# LED.net
KiCad netlist of a schematic drawn in Altium Designer
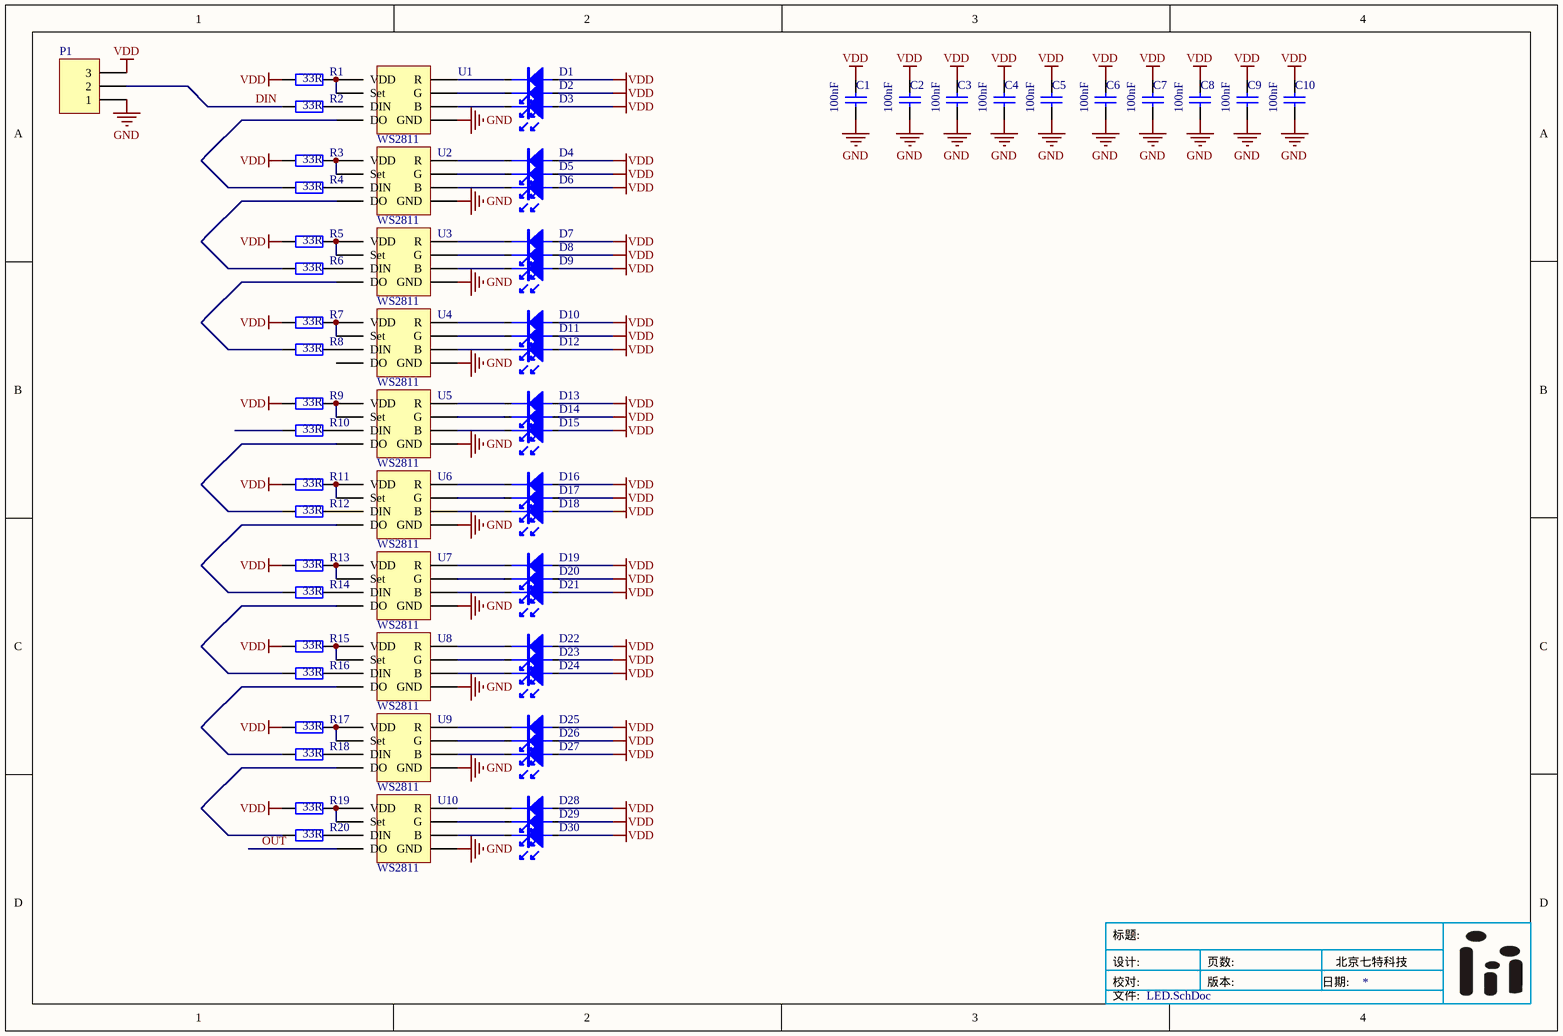
[diagram p0: LED.SchDoc]

(export (version "E")
  (design (tool "Eeschema 10.0.6"))
  (components
    (comp (ref "C1")
      (value "100nF")
      (footprint "1608C")
      (description "Capacitor")
      (fields (field (name "PUBLISHER") "Altium Limited"))
      (libsource (lib "*") (part "Cap"))
    )
    (comp (ref "C2")
      (value "100nF")
      (footprint "1608C")
      (description "Capacitor")
      (fields (field (name "PUBLISHER") "Altium Limited"))
      (libsource (lib "*") (part "Cap"))
    )
    (comp (ref "C3")
      (value "100nF")
      (footprint "1608C")
      (description "Capacitor")
      (fields (field (name "PUBLISHER") "Altium Limited"))
      (libsource (lib "*") (part "Cap"))
    )
    (comp (ref "C4")
      (value "100nF")
      (footprint "1608C")
      (description "Capacitor")
      (fields (field (name "PUBLISHER") "Altium Limited"))
      (libsource (lib "*") (part "Cap"))
    )
    (comp (ref "C5")
      (value "100nF")
      (footprint "1608C")
      (description "Capacitor")
      (fields (field (name "PUBLISHER") "Altium Limited"))
      (libsource (lib "*") (part "Cap"))
    )
    (comp (ref "C6")
      (value "100nF")
      (footprint "1608C")
      (description "Capacitor")
      (fields (field (name "PUBLISHER") "Altium Limited"))
      (libsource (lib "*") (part "Cap"))
    )
    (comp (ref "C7")
      (value "100nF")
      (footprint "1608C")
      (description "Capacitor")
      (fields (field (name "PUBLISHER") "Altium Limited"))
      (libsource (lib "*") (part "Cap"))
    )
    (comp (ref "C8")
      (value "100nF")
      (footprint "1608C")
      (description "Capacitor")
      (fields (field (name "PUBLISHER") "Altium Limited"))
      (libsource (lib "*") (part "Cap"))
    )
    (comp (ref "C9")
      (value "100nF")
      (footprint "1608C")
      (description "Capacitor")
      (fields (field (name "PUBLISHER") "Altium Limited"))
      (libsource (lib "*") (part "Cap"))
    )
    (comp (ref "C10")
      (value "100nF")
      (footprint "1608C")
      (description "Capacitor")
      (fields (field (name "PUBLISHER") "Altium Limited"))
      (libsource (lib "*") (part "Cap"))
    )
    (comp (ref "D1") (value "~") (footprint "LEDN/5S") (libsource (lib "*") (part "LED")))
    (comp (ref "D2") (value "~") (footprint "LEDN/5S") (libsource (lib "*") (part "LED")))
    (comp (ref "D3") (value "~") (footprint "LEDN/5S") (libsource (lib "*") (part "LED")))
    (comp (ref "D4") (value "~") (footprint "LEDN/5S") (libsource (lib "*") (part "LED")))
    (comp (ref "D5") (value "~") (footprint "LEDN/5S") (libsource (lib "*") (part "LED")))
    (comp (ref "D6") (value "~") (footprint "LEDN/5S") (libsource (lib "*") (part "LED")))
    (comp (ref "D7") (value "~") (footprint "LEDN/5S") (libsource (lib "*") (part "LED")))
    (comp (ref "D8") (value "~") (footprint "LEDN/5S") (libsource (lib "*") (part "LED")))
    (comp (ref "D9") (value "~") (footprint "LEDN/5S") (libsource (lib "*") (part "LED")))
    (comp (ref "D10") (value "~") (footprint "LEDN/5S") (libsource (lib "*") (part "LED")))
    (comp (ref "D11") (value "~") (footprint "LEDN/5S") (libsource (lib "*") (part "LED")))
    (comp (ref "D12") (value "~") (footprint "LEDN/5S") (libsource (lib "*") (part "LED")))
    (comp (ref "D13") (value "~") (footprint "LEDN/5S") (libsource (lib "*") (part "LED")))
    (comp (ref "D14") (value "~") (footprint "LEDN/5S") (libsource (lib "*") (part "LED")))
    (comp (ref "D15") (value "~") (footprint "LEDN/5S") (libsource (lib "*") (part "LED")))
    (comp (ref "D16") (value "~") (footprint "LEDN/5S") (libsource (lib "*") (part "LED")))
    (comp (ref "D17") (value "~") (footprint "LEDN/5S") (libsource (lib "*") (part "LED")))
    (comp (ref "D18") (value "~") (footprint "LEDN/5S") (libsource (lib "*") (part "LED")))
    (comp (ref "D19") (value "~") (footprint "LEDN/5S") (libsource (lib "*") (part "LED")))
    (comp (ref "D20") (value "~") (footprint "LEDN/5S") (libsource (lib "*") (part "LED")))
    (comp (ref "D21") (value "~") (footprint "LEDN/5S") (libsource (lib "*") (part "LED")))
    (comp (ref "D22") (value "~") (footprint "LEDN/5S") (libsource (lib "*") (part "LED")))
    (comp (ref "D23") (value "~") (footprint "LEDN/5S") (libsource (lib "*") (part "LED")))
    (comp (ref "D24") (value "~") (footprint "LEDN/5S") (libsource (lib "*") (part "LED")))
    (comp (ref "D25") (value "~") (footprint "LEDN/5S") (libsource (lib "*") (part "LED")))
    (comp (ref "D26") (value "~") (footprint "LEDN/5S") (libsource (lib "*") (part "LED")))
    (comp (ref "D27") (value "~") (footprint "LEDN/5S") (libsource (lib "*") (part "LED")))
    (comp (ref "D28") (value "~") (footprint "LEDN/5S") (libsource (lib "*") (part "LED")))
    (comp (ref "D29") (value "~") (footprint "LEDN/5S") (libsource (lib "*") (part "LED")))
    (comp (ref "D30") (value "~") (footprint "LEDN/5S") (libsource (lib "*") (part "LED")))
    (comp (ref "P1")
      (value "~")
      (footprint "5264-3")
      (description "Header, 3-Pin")
      (fields (field (name "PUBLISHER") "Altium Limited"))
      (libsource (lib "Miscellaneous Connectors") (part "Header 3"))
    )
    (comp (ref "R1")
      (value "33R")
      (footprint "1608")
      (description "Resistor")
      (fields (field (name "PUBLISHER") "Altium Limited"))
      (libsource (lib "*") (part "Res2"))
    )
    (comp (ref "R2")
      (value "33R")
      (footprint "1608")
      (description "Resistor")
      (fields (field (name "PUBLISHER") "Altium Limited"))
      (libsource (lib "*") (part "Res2"))
    )
    (comp (ref "R3")
      (value "33R")
      (footprint "1608")
      (description "Resistor")
      (fields (field (name "PUBLISHER") "Altium Limited"))
      (libsource (lib "*") (part "Res2"))
    )
    (comp (ref "R4")
      (value "33R")
      (footprint "1608")
      (description "Resistor")
      (fields (field (name "PUBLISHER") "Altium Limited"))
      (libsource (lib "*") (part "Res2"))
    )
    (comp (ref "R5")
      (value "33R")
      (footprint "1608")
      (description "Resistor")
      (fields (field (name "PUBLISHER") "Altium Limited"))
      (libsource (lib "*") (part "Res2"))
    )
    (comp (ref "R6")
      (value "33R")
      (footprint "1608")
      (description "Resistor")
      (fields (field (name "PUBLISHER") "Altium Limited"))
      (libsource (lib "*") (part "Res2"))
    )
    (comp (ref "R7")
      (value "33R")
      (footprint "1608")
      (description "Resistor")
      (fields (field (name "PUBLISHER") "Altium Limited"))
      (libsource (lib "*") (part "Res2"))
    )
    (comp (ref "R8")
      (value "33R")
      (footprint "1608")
      (description "Resistor")
      (fields (field (name "PUBLISHER") "Altium Limited"))
      (libsource (lib "*") (part "Res2"))
    )
    (comp (ref "R9")
      (value "33R")
      (footprint "1608")
      (description "Resistor")
      (fields (field (name "PUBLISHER") "Altium Limited"))
      (libsource (lib "*") (part "Res2"))
    )
    (comp (ref "R10")
      (value "33R")
      (footprint "1608")
      (description "Resistor")
      (fields (field (name "PUBLISHER") "Altium Limited"))
      (libsource (lib "*") (part "Res2"))
    )
    (comp (ref "R11")
      (value "33R")
      (footprint "1608")
      (description "Resistor")
      (fields (field (name "PUBLISHER") "Altium Limited"))
      (libsource (lib "*") (part "Res2"))
    )
    (comp (ref "R12")
      (value "33R")
      (footprint "1608")
      (description "Resistor")
      (fields (field (name "PUBLISHER") "Altium Limited"))
      (libsource (lib "*") (part "Res2"))
    )
    (comp (ref "R13")
      (value "33R")
      (footprint "1608")
      (description "Resistor")
      (fields (field (name "PUBLISHER") "Altium Limited"))
      (libsource (lib "*") (part "Res2"))
    )
    (comp (ref "R14")
      (value "33R")
      (footprint "1608")
      (description "Resistor")
      (fields (field (name "PUBLISHER") "Altium Limited"))
      (libsource (lib "*") (part "Res2"))
    )
    (comp (ref "R15")
      (value "33R")
      (footprint "1608")
      (description "Resistor")
      (fields (field (name "PUBLISHER") "Altium Limited"))
      (libsource (lib "*") (part "Res2"))
    )
    (comp (ref "R16")
      (value "33R")
      (footprint "1608")
      (description "Resistor")
      (fields (field (name "PUBLISHER") "Altium Limited"))
      (libsource (lib "*") (part "Res2"))
    )
    (comp (ref "R17")
      (value "33R")
      (footprint "1608")
      (description "Resistor")
      (fields (field (name "PUBLISHER") "Altium Limited"))
      (libsource (lib "*") (part "Res2"))
    )
    (comp (ref "R18")
      (value "33R")
      (footprint "1608")
      (description "Resistor")
      (fields (field (name "PUBLISHER") "Altium Limited"))
      (libsource (lib "*") (part "Res2"))
    )
    (comp (ref "R19")
      (value "33R")
      (footprint "1608")
      (description "Resistor")
      (fields (field (name "PUBLISHER") "Altium Limited"))
      (libsource (lib "*") (part "Res2"))
    )
    (comp (ref "R20")
      (value "33R")
      (footprint "1608")
      (description "Resistor")
      (fields (field (name "PUBLISHER") "Altium Limited"))
      (libsource (lib "*") (part "Res2"))
    )
    (comp (ref "U1")
      (value "WS2811")
      (footprint "so8")
      (description "Header, 4-Pin, Dual row")
      (fields (field (name "PUBLISHER") "Altium Limited"))
      (libsource (lib "Miscellaneous Connectors") (part "Header 4X2"))
    )
    (comp (ref "U2")
      (value "WS2811")
      (footprint "so8")
      (description "Header, 4-Pin, Dual row")
      (fields (field (name "PUBLISHER") "Altium Limited"))
      (libsource (lib "Miscellaneous Connectors") (part "Header 4X2"))
    )
    (comp (ref "U3")
      (value "WS2811")
      (footprint "so8")
      (description "Header, 4-Pin, Dual row")
      (fields (field (name "PUBLISHER") "Altium Limited"))
      (libsource (lib "Miscellaneous Connectors") (part "Header 4X2"))
    )
    (comp (ref "U4")
      (value "WS2811")
      (footprint "so8")
      (description "Header, 4-Pin, Dual row")
      (fields (field (name "PUBLISHER") "Altium Limited"))
      (libsource (lib "Miscellaneous Connectors") (part "Header 4X2"))
    )
    (comp (ref "U5")
      (value "WS2811")
      (footprint "so8")
      (description "Header, 4-Pin, Dual row")
      (fields (field (name "PUBLISHER") "Altium Limited"))
      (libsource (lib "Miscellaneous Connectors") (part "Header 4X2"))
    )
    (comp (ref "U6")
      (value "WS2811")
      (footprint "so8")
      (description "Header, 4-Pin, Dual row")
      (fields (field (name "PUBLISHER") "Altium Limited"))
      (libsource (lib "Miscellaneous Connectors") (part "Header 4X2"))
    )
    (comp (ref "U7")
      (value "WS2811")
      (footprint "so8")
      (description "Header, 4-Pin, Dual row")
      (fields (field (name "PUBLISHER") "Altium Limited"))
      (libsource (lib "Miscellaneous Connectors") (part "Header 4X2"))
    )
    (comp (ref "U8")
      (value "WS2811")
      (footprint "so8")
      (description "Header, 4-Pin, Dual row")
      (fields (field (name "PUBLISHER") "Altium Limited"))
      (libsource (lib "Miscellaneous Connectors") (part "Header 4X2"))
    )
    (comp (ref "U9")
      (value "WS2811")
      (footprint "so8")
      (description "Header, 4-Pin, Dual row")
      (fields (field (name "PUBLISHER") "Altium Limited"))
      (libsource (lib "Miscellaneous Connectors") (part "Header 4X2"))
    )
    (comp (ref "U10")
      (value "WS2811")
      (footprint "so8")
      (description "Header, 4-Pin, Dual row")
      (fields (field (name "PUBLISHER") "Altium Limited"))
      (libsource (lib "Miscellaneous Connectors") (part "Header 4X2"))
    )
  )
  (nets
    (net (code "1") (name "/DIN") (class "Default")
      (node (ref "P1") (pin "2") (pinfunction "2_2") (pintype "passive"))
      (node (ref "R2") (pin "2") (pinfunction "2_2") (pintype "passive"))
    )
    (net (code "2") (name "/OUT") (class "Default")
      (node (ref "U10") (pin "5") (pinfunction "DO_5") (pintype "passive"))
    )
    (net (code "3") (name "GND") (class "Default")
      (node (ref "C1") (pin "1") (pinfunction "1_1") (pintype "passive"))
      (node (ref "C10") (pin "1") (pinfunction "1_1") (pintype "passive"))
      (node (ref "C2") (pin "1") (pinfunction "1_1") (pintype "passive"))
      (node (ref "C3") (pin "1") (pinfunction "1_1") (pintype "passive"))
      (node (ref "C4") (pin "1") (pinfunction "1_1") (pintype "passive"))
      (node (ref "C5") (pin "1") (pinfunction "1_1") (pintype "passive"))
      (node (ref "C6") (pin "1") (pinfunction "1_1") (pintype "passive"))
      (node (ref "C7") (pin "1") (pinfunction "1_1") (pintype "passive"))
      (node (ref "C8") (pin "1") (pinfunction "1_1") (pintype "passive"))
      (node (ref "C9") (pin "1") (pinfunction "1_1") (pintype "passive"))
      (node (ref "P1") (pin "1") (pinfunction "1_1") (pintype "passive"))
      (node (ref "U1") (pin "4") (pinfunction "GND_4") (pintype "passive"))
      (node (ref "U10") (pin "4") (pinfunction "GND_4") (pintype "passive"))
      (node (ref "U2") (pin "4") (pinfunction "GND_4") (pintype "passive"))
      (node (ref "U3") (pin "4") (pinfunction "GND_4") (pintype "passive"))
      (node (ref "U4") (pin "4") (pinfunction "GND_4") (pintype "passive"))
      (node (ref "U5") (pin "4") (pinfunction "GND_4") (pintype "passive"))
      (node (ref "U6") (pin "4") (pinfunction "GND_4") (pintype "passive"))
      (node (ref "U7") (pin "4") (pinfunction "GND_4") (pintype "passive"))
      (node (ref "U8") (pin "4") (pinfunction "GND_4") (pintype "passive"))
      (node (ref "U9") (pin "4") (pinfunction "GND_4") (pintype "passive"))
    )
    (net (code "4") (name "Net-(U1-B)") (class "Default")
      (node (ref "D3") (pin "2") (pintype "passive"))
      (node (ref "U1") (pin "3") (pinfunction "B_3") (pintype "passive"))
    )
    (net (code "5") (name "Net-(U1-DIN)") (class "Default")
      (node (ref "R2") (pin "1") (pinfunction "1_1") (pintype "passive"))
      (node (ref "U1") (pin "6") (pinfunction "DIN_6") (pintype "passive"))
    )
    (net (code "6") (name "Net-(U1-DO)") (class "Default")
      (node (ref "R4") (pin "2") (pinfunction "2_2") (pintype "passive"))
      (node (ref "U1") (pin "5") (pinfunction "DO_5") (pintype "passive"))
    )
    (net (code "7") (name "Net-(U1-G)") (class "Default")
      (node (ref "D2") (pin "2") (pintype "passive"))
      (node (ref "U1") (pin "2") (pinfunction "G_2") (pintype "passive"))
    )
    (net (code "8") (name "Net-(U1-R)") (class "Default")
      (node (ref "D1") (pin "2") (pintype "passive"))
      (node (ref "U1") (pin "1") (pinfunction "R_1") (pintype "passive"))
    )
    (net (code "9") (name "Net-(U1-Set)") (class "Default")
      (node (ref "R1") (pin "1") (pinfunction "1_1") (pintype "passive"))
      (node (ref "U1") (pin "7") (pinfunction "Set_7") (pintype "passive"))
      (node (ref "U1") (pin "8") (pinfunction "VDD_8") (pintype "passive"))
    )
    (net (code "10") (name "Net-(U2-B)") (class "Default")
      (node (ref "D6") (pin "2") (pintype "passive"))
      (node (ref "U2") (pin "3") (pinfunction "B_3") (pintype "passive"))
    )
    (net (code "11") (name "Net-(U2-DIN)") (class "Default")
      (node (ref "R4") (pin "1") (pinfunction "1_1") (pintype "passive"))
      (node (ref "U2") (pin "6") (pinfunction "DIN_6") (pintype "passive"))
    )
    (net (code "12") (name "Net-(U2-DO)") (class "Default")
      (node (ref "R6") (pin "2") (pinfunction "2_2") (pintype "passive"))
      (node (ref "U2") (pin "5") (pinfunction "DO_5") (pintype "passive"))
    )
    (net (code "13") (name "Net-(U2-G)") (class "Default")
      (node (ref "D5") (pin "2") (pintype "passive"))
      (node (ref "U2") (pin "2") (pinfunction "G_2") (pintype "passive"))
    )
    (net (code "14") (name "Net-(U2-R)") (class "Default")
      (node (ref "D4") (pin "2") (pintype "passive"))
      (node (ref "U2") (pin "1") (pinfunction "R_1") (pintype "passive"))
    )
    (net (code "15") (name "Net-(U2-Set)") (class "Default")
      (node (ref "R3") (pin "1") (pinfunction "1_1") (pintype "passive"))
      (node (ref "U2") (pin "7") (pinfunction "Set_7") (pintype "passive"))
      (node (ref "U2") (pin "8") (pinfunction "VDD_8") (pintype "passive"))
    )
    (net (code "16") (name "Net-(U3-B)") (class "Default")
      (node (ref "D9") (pin "2") (pintype "passive"))
      (node (ref "U3") (pin "3") (pinfunction "B_3") (pintype "passive"))
    )
    (net (code "17") (name "Net-(U3-DIN)") (class "Default")
      (node (ref "R6") (pin "1") (pinfunction "1_1") (pintype "passive"))
      (node (ref "U3") (pin "6") (pinfunction "DIN_6") (pintype "passive"))
    )
    (net (code "18") (name "Net-(U3-DO)") (class "Default")
      (node (ref "R8") (pin "2") (pinfunction "2_2") (pintype "passive"))
      (node (ref "U3") (pin "5") (pinfunction "DO_5") (pintype "passive"))
    )
    (net (code "19") (name "Net-(U3-G)") (class "Default")
      (node (ref "D8") (pin "2") (pintype "passive"))
      (node (ref "U3") (pin "2") (pinfunction "G_2") (pintype "passive"))
    )
    (net (code "20") (name "Net-(U3-R)") (class "Default")
      (node (ref "D7") (pin "2") (pintype "passive"))
      (node (ref "U3") (pin "1") (pinfunction "R_1") (pintype "passive"))
    )
    (net (code "21") (name "Net-(U3-Set)") (class "Default")
      (node (ref "R5") (pin "1") (pinfunction "1_1") (pintype "passive"))
      (node (ref "U3") (pin "7") (pinfunction "Set_7") (pintype "passive"))
      (node (ref "U3") (pin "8") (pinfunction "VDD_8") (pintype "passive"))
    )
    (net (code "22") (name "Net-(U4-B)") (class "Default")
      (node (ref "D12") (pin "2") (pintype "passive"))
      (node (ref "U4") (pin "3") (pinfunction "B_3") (pintype "passive"))
    )
    (net (code "23") (name "Net-(U4-DIN)") (class "Default")
      (node (ref "R8") (pin "1") (pinfunction "1_1") (pintype "passive"))
      (node (ref "U4") (pin "6") (pinfunction "DIN_6") (pintype "passive"))
    )
    (net (code "24") (name "Net-(U4-G)") (class "Default")
      (node (ref "D11") (pin "2") (pintype "passive"))
      (node (ref "U4") (pin "2") (pinfunction "G_2") (pintype "passive"))
    )
    (net (code "25") (name "Net-(U4-R)") (class "Default")
      (node (ref "D10") (pin "2") (pintype "passive"))
      (node (ref "U4") (pin "1") (pinfunction "R_1") (pintype "passive"))
    )
    (net (code "26") (name "Net-(U4-Set)") (class "Default")
      (node (ref "R7") (pin "1") (pinfunction "1_1") (pintype "passive"))
      (node (ref "U4") (pin "7") (pinfunction "Set_7") (pintype "passive"))
      (node (ref "U4") (pin "8") (pinfunction "VDD_8") (pintype "passive"))
    )
    (net (code "27") (name "Net-(U5-B)") (class "Default")
      (node (ref "D15") (pin "2") (pintype "passive"))
      (node (ref "U5") (pin "3") (pinfunction "B_3") (pintype "passive"))
    )
    (net (code "28") (name "Net-(U5-DIN)") (class "Default")
      (node (ref "R10") (pin "1") (pinfunction "1_1") (pintype "passive"))
      (node (ref "U5") (pin "6") (pinfunction "DIN_6") (pintype "passive"))
    )
    (net (code "29") (name "Net-(U5-DO)") (class "Default")
      (node (ref "R12") (pin "2") (pinfunction "2_2") (pintype "passive"))
      (node (ref "U5") (pin "5") (pinfunction "DO_5") (pintype "passive"))
    )
    (net (code "30") (name "Net-(U5-G)") (class "Default")
      (node (ref "D14") (pin "2") (pintype "passive"))
      (node (ref "U5") (pin "2") (pinfunction "G_2") (pintype "passive"))
    )
    (net (code "31") (name "Net-(U5-R)") (class "Default")
      (node (ref "D13") (pin "2") (pintype "passive"))
      (node (ref "U5") (pin "1") (pinfunction "R_1") (pintype "passive"))
    )
    (net (code "32") (name "Net-(U5-Set)") (class "Default")
      (node (ref "R9") (pin "1") (pinfunction "1_1") (pintype "passive"))
      (node (ref "U5") (pin "7") (pinfunction "Set_7") (pintype "passive"))
      (node (ref "U5") (pin "8") (pinfunction "VDD_8") (pintype "passive"))
    )
    (net (code "33") (name "Net-(U6-B)") (class "Default")
      (node (ref "D18") (pin "2") (pintype "passive"))
      (node (ref "U6") (pin "3") (pinfunction "B_3") (pintype "passive"))
    )
    (net (code "34") (name "Net-(U6-DIN)") (class "Default")
      (node (ref "R12") (pin "1") (pinfunction "1_1") (pintype "passive"))
      (node (ref "U6") (pin "6") (pinfunction "DIN_6") (pintype "passive"))
    )
    (net (code "35") (name "Net-(U6-DO)") (class "Default")
      (node (ref "R14") (pin "2") (pinfunction "2_2") (pintype "passive"))
      (node (ref "U6") (pin "5") (pinfunction "DO_5") (pintype "passive"))
    )
    (net (code "36") (name "Net-(U6-G)") (class "Default")
      (node (ref "D17") (pin "2") (pintype "passive"))
      (node (ref "U6") (pin "2") (pinfunction "G_2") (pintype "passive"))
    )
    (net (code "37") (name "Net-(U6-R)") (class "Default")
      (node (ref "D16") (pin "2") (pintype "passive"))
      (node (ref "U6") (pin "1") (pinfunction "R_1") (pintype "passive"))
    )
    (net (code "38") (name "Net-(U6-Set)") (class "Default")
      (node (ref "R11") (pin "1") (pinfunction "1_1") (pintype "passive"))
      (node (ref "U6") (pin "7") (pinfunction "Set_7") (pintype "passive"))
      (node (ref "U6") (pin "8") (pinfunction "VDD_8") (pintype "passive"))
    )
    (net (code "39") (name "Net-(U7-B)") (class "Default")
      (node (ref "D21") (pin "2") (pintype "passive"))
      (node (ref "U7") (pin "3") (pinfunction "B_3") (pintype "passive"))
    )
    (net (code "40") (name "Net-(U7-DIN)") (class "Default")
      (node (ref "R14") (pin "1") (pinfunction "1_1") (pintype "passive"))
      (node (ref "U7") (pin "6") (pinfunction "DIN_6") (pintype "passive"))
    )
    (net (code "41") (name "Net-(U7-DO)") (class "Default")
      (node (ref "R16") (pin "2") (pinfunction "2_2") (pintype "passive"))
      (node (ref "U7") (pin "5") (pinfunction "DO_5") (pintype "passive"))
    )
    (net (code "42") (name "Net-(U7-G)") (class "Default")
      (node (ref "D20") (pin "2") (pintype "passive"))
      (node (ref "U7") (pin "2") (pinfunction "G_2") (pintype "passive"))
    )
    (net (code "43") (name "Net-(U7-R)") (class "Default")
      (node (ref "D19") (pin "2") (pintype "passive"))
      (node (ref "U7") (pin "1") (pinfunction "R_1") (pintype "passive"))
    )
    (net (code "44") (name "Net-(U7-Set)") (class "Default")
      (node (ref "R13") (pin "1") (pinfunction "1_1") (pintype "passive"))
      (node (ref "U7") (pin "7") (pinfunction "Set_7") (pintype "passive"))
      (node (ref "U7") (pin "8") (pinfunction "VDD_8") (pintype "passive"))
    )
    (net (code "45") (name "Net-(U8-B)") (class "Default")
      (node (ref "D24") (pin "2") (pintype "passive"))
      (node (ref "U8") (pin "3") (pinfunction "B_3") (pintype "passive"))
    )
    (net (code "46") (name "Net-(U8-DIN)") (class "Default")
      (node (ref "R16") (pin "1") (pinfunction "1_1") (pintype "passive"))
      (node (ref "U8") (pin "6") (pinfunction "DIN_6") (pintype "passive"))
    )
    (net (code "47") (name "Net-(U8-DO)") (class "Default")
      (node (ref "R18") (pin "2") (pinfunction "2_2") (pintype "passive"))
      (node (ref "U8") (pin "5") (pinfunction "DO_5") (pintype "passive"))
    )
    (net (code "48") (name "Net-(U8-G)") (class "Default")
      (node (ref "D23") (pin "2") (pintype "passive"))
      (node (ref "U8") (pin "2") (pinfunction "G_2") (pintype "passive"))
    )
    (net (code "49") (name "Net-(U8-R)") (class "Default")
      (node (ref "D22") (pin "2") (pintype "passive"))
      (node (ref "U8") (pin "1") (pinfunction "R_1") (pintype "passive"))
    )
    (net (code "50") (name "Net-(U8-Set)") (class "Default")
      (node (ref "R15") (pin "1") (pinfunction "1_1") (pintype "passive"))
      (node (ref "U8") (pin "7") (pinfunction "Set_7") (pintype "passive"))
      (node (ref "U8") (pin "8") (pinfunction "VDD_8") (pintype "passive"))
    )
    (net (code "51") (name "Net-(U9-B)") (class "Default")
      (node (ref "D27") (pin "2") (pintype "passive"))
      (node (ref "U9") (pin "3") (pinfunction "B_3") (pintype "passive"))
    )
    (net (code "52") (name "Net-(U9-DIN)") (class "Default")
      (node (ref "R18") (pin "1") (pinfunction "1_1") (pintype "passive"))
      (node (ref "U9") (pin "6") (pinfunction "DIN_6") (pintype "passive"))
    )
    (net (code "53") (name "Net-(U9-DO)") (class "Default")
      (node (ref "R20") (pin "2") (pinfunction "2_2") (pintype "passive"))
      (node (ref "U9") (pin "5") (pinfunction "DO_5") (pintype "passive"))
    )
    (net (code "54") (name "Net-(U9-G)") (class "Default")
      (node (ref "D26") (pin "2") (pintype "passive"))
      (node (ref "U9") (pin "2") (pinfunction "G_2") (pintype "passive"))
    )
    (net (code "55") (name "Net-(U9-R)") (class "Default")
      (node (ref "D25") (pin "2") (pintype "passive"))
      (node (ref "U9") (pin "1") (pinfunction "R_1") (pintype "passive"))
    )
    (net (code "56") (name "Net-(U9-Set)") (class "Default")
      (node (ref "R17") (pin "1") (pinfunction "1_1") (pintype "passive"))
      (node (ref "U9") (pin "7") (pinfunction "Set_7") (pintype "passive"))
      (node (ref "U9") (pin "8") (pinfunction "VDD_8") (pintype "passive"))
    )
    (net (code "57") (name "Net-(U10-B)") (class "Default")
      (node (ref "D30") (pin "2") (pintype "passive"))
      (node (ref "U10") (pin "3") (pinfunction "B_3") (pintype "passive"))
    )
    (net (code "58") (name "Net-(U10-DIN)") (class "Default")
      (node (ref "R20") (pin "1") (pinfunction "1_1") (pintype "passive"))
      (node (ref "U10") (pin "6") (pinfunction "DIN_6") (pintype "passive"))
    )
    (net (code "59") (name "Net-(U10-G)") (class "Default")
      (node (ref "D29") (pin "2") (pintype "passive"))
      (node (ref "U10") (pin "2") (pinfunction "G_2") (pintype "passive"))
    )
    (net (code "60") (name "Net-(U10-R)") (class "Default")
      (node (ref "D28") (pin "2") (pintype "passive"))
      (node (ref "U10") (pin "1") (pinfunction "R_1") (pintype "passive"))
    )
    (net (code "61") (name "Net-(U10-Set)") (class "Default")
      (node (ref "R19") (pin "1") (pinfunction "1_1") (pintype "passive"))
      (node (ref "U10") (pin "7") (pinfunction "Set_7") (pintype "passive"))
      (node (ref "U10") (pin "8") (pinfunction "VDD_8") (pintype "passive"))
    )
    (net (code "62") (name "VDD") (class "Default")
      (node (ref "C1") (pin "2") (pinfunction "2_2") (pintype "passive"))
      (node (ref "C10") (pin "2") (pinfunction "2_2") (pintype "passive"))
      (node (ref "C2") (pin "2") (pinfunction "2_2") (pintype "passive"))
      (node (ref "C3") (pin "2") (pinfunction "2_2") (pintype "passive"))
      (node (ref "C4") (pin "2") (pinfunction "2_2") (pintype "passive"))
      (node (ref "C5") (pin "2") (pinfunction "2_2") (pintype "passive"))
      (node (ref "C6") (pin "2") (pinfunction "2_2") (pintype "passive"))
      (node (ref "C7") (pin "2") (pinfunction "2_2") (pintype "passive"))
      (node (ref "C8") (pin "2") (pinfunction "2_2") (pintype "passive"))
      (node (ref "C9") (pin "2") (pinfunction "2_2") (pintype "passive"))
      (node (ref "D1") (pin "1") (pintype "passive"))
      (node (ref "D10") (pin "1") (pintype "passive"))
      (node (ref "D11") (pin "1") (pintype "passive"))
      (node (ref "D12") (pin "1") (pintype "passive"))
      (node (ref "D13") (pin "1") (pintype "passive"))
      (node (ref "D14") (pin "1") (pintype "passive"))
      (node (ref "D15") (pin "1") (pintype "passive"))
      (node (ref "D16") (pin "1") (pintype "passive"))
      (node (ref "D17") (pin "1") (pintype "passive"))
      (node (ref "D18") (pin "1") (pintype "passive"))
      (node (ref "D19") (pin "1") (pintype "passive"))
      (node (ref "D2") (pin "1") (pintype "passive"))
      (node (ref "D20") (pin "1") (pintype "passive"))
      (node (ref "D21") (pin "1") (pintype "passive"))
      (node (ref "D22") (pin "1") (pintype "passive"))
      (node (ref "D23") (pin "1") (pintype "passive"))
      (node (ref "D24") (pin "1") (pintype "passive"))
      (node (ref "D25") (pin "1") (pintype "passive"))
      (node (ref "D26") (pin "1") (pintype "passive"))
      (node (ref "D27") (pin "1") (pintype "passive"))
      (node (ref "D28") (pin "1") (pintype "passive"))
      (node (ref "D29") (pin "1") (pintype "passive"))
      (node (ref "D3") (pin "1") (pintype "passive"))
      (node (ref "D30") (pin "1") (pintype "passive"))
      (node (ref "D4") (pin "1") (pintype "passive"))
      (node (ref "D5") (pin "1") (pintype "passive"))
      (node (ref "D6") (pin "1") (pintype "passive"))
      (node (ref "D7") (pin "1") (pintype "passive"))
      (node (ref "D8") (pin "1") (pintype "passive"))
      (node (ref "D9") (pin "1") (pintype "passive"))
      (node (ref "P1") (pin "3") (pinfunction "3_3") (pintype "passive"))
      (node (ref "R1") (pin "2") (pinfunction "2_2") (pintype "passive"))
      (node (ref "R11") (pin "2") (pinfunction "2_2") (pintype "passive"))
      (node (ref "R13") (pin "2") (pinfunction "2_2") (pintype "passive"))
      (node (ref "R15") (pin "2") (pinfunction "2_2") (pintype "passive"))
      (node (ref "R17") (pin "2") (pinfunction "2_2") (pintype "passive"))
      (node (ref "R19") (pin "2") (pinfunction "2_2") (pintype "passive"))
      (node (ref "R3") (pin "2") (pinfunction "2_2") (pintype "passive"))
      (node (ref "R5") (pin "2") (pinfunction "2_2") (pintype "passive"))
      (node (ref "R7") (pin "2") (pinfunction "2_2") (pintype "passive"))
      (node (ref "R9") (pin "2") (pinfunction "2_2") (pintype "passive"))
    )
    (net (code "63") (name "unconnected-(R10-Pad2)") (class "Default")
      (node (ref "R10") (pin "2") (pinfunction "2_2") (pintype "passive"))
    )
    (net (code "64") (name "unconnected-(U4-DO-Pad5)") (class "Default")
      (node (ref "U4") (pin "5") (pinfunction "DO_5") (pintype "passive"))
    )
  )
)
